# High_Power_Output.net
KiCad netlist of a schematic drawn in Altium Designer
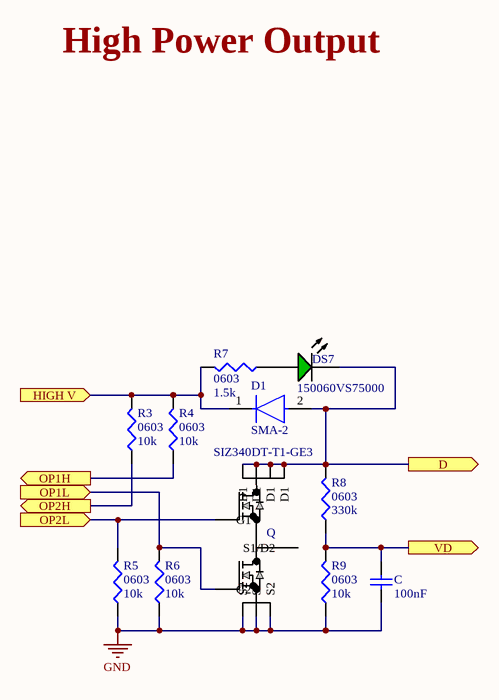
[diagram p0: High Power Output.SchDoc]

(export (version "E")
  (design (tool "Eeschema 10.0.6"))
  (components
    (comp (ref "C")
      (value "100nF")
      (footprint "CAPC1608X95X40ML15T15")
      (fields (field (name "MANUFACTURER") "Vitramon") (field (name "PART NUMBER") "VJ0603Y104KXQCW1BC"))
      (libsource (lib "Altium Content Vault") (part "CAP"))
    )
    (comp (ref "D1")
      (value "SMA-2")
      (footprint "FP-DO-214AC-MFG")
      (description "DIODE GEN PURP 1.6KV 1A DO214AC")
      (libsource (lib "Altium Content Vault") (part "d7152d700b627762746794eb795d46e"))
    )
    (comp (ref "DS7")
      (value "150060VS75000")
      (footprint "WE-150060VS75000_V")
      (libsource (lib "Altium Content Vault") (part "LED_GREEN_K1A2-2"))
    )
    (comp (ref "Q")
      (value "SIZ340DT-T1-GE3")
      (footprint "MOSFET_DT-T1-GE3_VIS")
      (description "No Description Available")
      (fields (field (name "COPYRIGHT") "Copyright (C) 2022 Ultra Librarian. All rights reserved."))
      (libsource (lib "SIZ340DT-T1-GE3") (part "SIZ340DT-T1-GE3"))
    )
    (comp (ref "R3")
      (value "0603")
      (footprint "J1-0603")
      (description "Resistor")
      (fields (field (name "ALTIUM_VALUE") "10k") (field (name "PUBLISHER") "Altium Limited"))
      (libsource (lib "Miscellaneous Devices") (part "Res3"))
    )
    (comp (ref "R4")
      (value "0603")
      (footprint "J1-0603")
      (description "Resistor")
      (fields (field (name "ALTIUM_VALUE") "10k") (field (name "PUBLISHER") "Altium Limited"))
      (libsource (lib "Miscellaneous Devices") (part "Res3"))
    )
    (comp (ref "R5")
      (value "0603")
      (footprint "J1-0603")
      (description "Resistor")
      (fields (field (name "ALTIUM_VALUE") "10k") (field (name "PUBLISHER") "Altium Limited"))
      (libsource (lib "Miscellaneous Devices") (part "Res3"))
    )
    (comp (ref "R6")
      (value "0603")
      (footprint "J1-0603")
      (description "Resistor")
      (fields (field (name "ALTIUM_VALUE") "10k") (field (name "PUBLISHER") "Altium Limited"))
      (libsource (lib "Miscellaneous Devices") (part "Res3"))
    )
    (comp (ref "R7")
      (value "0603")
      (footprint "J1-0603")
      (description "Resistor")
      (fields (field (name "ALTIUM_VALUE") "1.5k") (field (name "PUBLISHER") "Altium Limited"))
      (libsource (lib "Miscellaneous Devices") (part "Res3"))
    )
    (comp (ref "R8")
      (value "0603")
      (footprint "J1-0603")
      (description "Resistor")
      (fields (field (name "ALTIUM_VALUE") "330k") (field (name "PUBLISHER") "Altium Limited"))
      (libsource (lib "Miscellaneous Devices") (part "Res3"))
    )
    (comp (ref "R9")
      (value "0603")
      (footprint "J1-0603")
      (description "Resistor")
      (fields (field (name "ALTIUM_VALUE") "10k") (field (name "PUBLISHER") "Altium Limited"))
      (libsource (lib "Miscellaneous Devices") (part "Res3"))
    )
  )
  (nets
    (net (code "1") (name "/D") (class "Default")
      (node (ref "D1") (pin "2") (pinfunction "A_2") (pintype "passive"))
      (node (ref "DS7") (pin "1") (pinfunction "K_1") (pintype "passive"))
      (node (ref "Q") (pin "10") (pinfunction "D1_10") (pintype "bidirectional"))
      (node (ref "Q") (pin "2") (pinfunction "D1_2") (pintype "bidirectional"))
      (node (ref "Q") (pin "3") (pinfunction "D1_3") (pintype "bidirectional"))
      (node (ref "Q") (pin "4") (pinfunction "D1_4") (pintype "bidirectional"))
      (node (ref "R8") (pin "2") (pinfunction "2_2") (pintype "passive"))
    )
    (net (code "2") (name "/HIGH V") (class "Default")
      (node (ref "D1") (pin "1") (pinfunction "C_1") (pintype "passive"))
      (node (ref "R3") (pin "2") (pinfunction "2_2") (pintype "passive"))
      (node (ref "R4") (pin "2") (pinfunction "2_2") (pintype "passive"))
      (node (ref "R7") (pin "2") (pinfunction "2_2") (pintype "passive"))
    )
    (net (code "3") (name "/OP1H") (class "Default")
      (node (ref "R4") (pin "1") (pinfunction "1_1") (pintype "passive"))
    )
    (net (code "4") (name "/OP1L") (class "Default")
      (node (ref "Q") (pin "8") (pinfunction "G2_8") (pintype "bidirectional"))
      (node (ref "R6") (pin "2") (pinfunction "2_2") (pintype "passive"))
    )
    (net (code "5") (name "/OP2H") (class "Default")
      (node (ref "R3") (pin "1") (pinfunction "1_1") (pintype "passive"))
    )
    (net (code "6") (name "/OP2L") (class "Default")
      (node (ref "Q") (pin "1") (pinfunction "G1_1") (pintype "bidirectional"))
      (node (ref "R5") (pin "2") (pinfunction "2_2") (pintype "passive"))
    )
    (net (code "7") (name "/VD") (class "Default")
      (node (ref "C") (pin "2") (pinfunction "2_2") (pintype "passive"))
      (node (ref "R8") (pin "1") (pinfunction "1_1") (pintype "passive"))
      (node (ref "R9") (pin "2") (pinfunction "2_2") (pintype "passive"))
    )
    (net (code "8") (name "GND") (class "Default")
      (node (ref "C") (pin "1") (pinfunction "1_1") (pintype "passive"))
      (node (ref "Q") (pin "5") (pinfunction "S2_5") (pintype "bidirectional"))
      (node (ref "Q") (pin "6") (pinfunction "S2_6") (pintype "bidirectional"))
      (node (ref "Q") (pin "7") (pinfunction "S2_7") (pintype "passive"))
      (node (ref "R5") (pin "1") (pinfunction "1_1") (pintype "passive"))
      (node (ref "R6") (pin "1") (pinfunction "1_1") (pintype "passive"))
      (node (ref "R9") (pin "1") (pinfunction "1_1") (pintype "passive"))
    )
    (net (code "9") (name "Net-(DS7-A)") (class "Default")
      (node (ref "DS7") (pin "2") (pinfunction "A_2") (pintype "passive"))
      (node (ref "R7") (pin "1") (pinfunction "1_1") (pintype "passive"))
    )
    (net (code "10") (name "unconnected-(Q-S1{slash}D2-Pad9)") (class "Default")
      (node (ref "Q") (pin "9") (pinfunction "S1/D2_9") (pintype "bidirectional"))
    )
  )
)
